# BBUNO.net
KiCad netlist of a schematic drawn in EAGLE
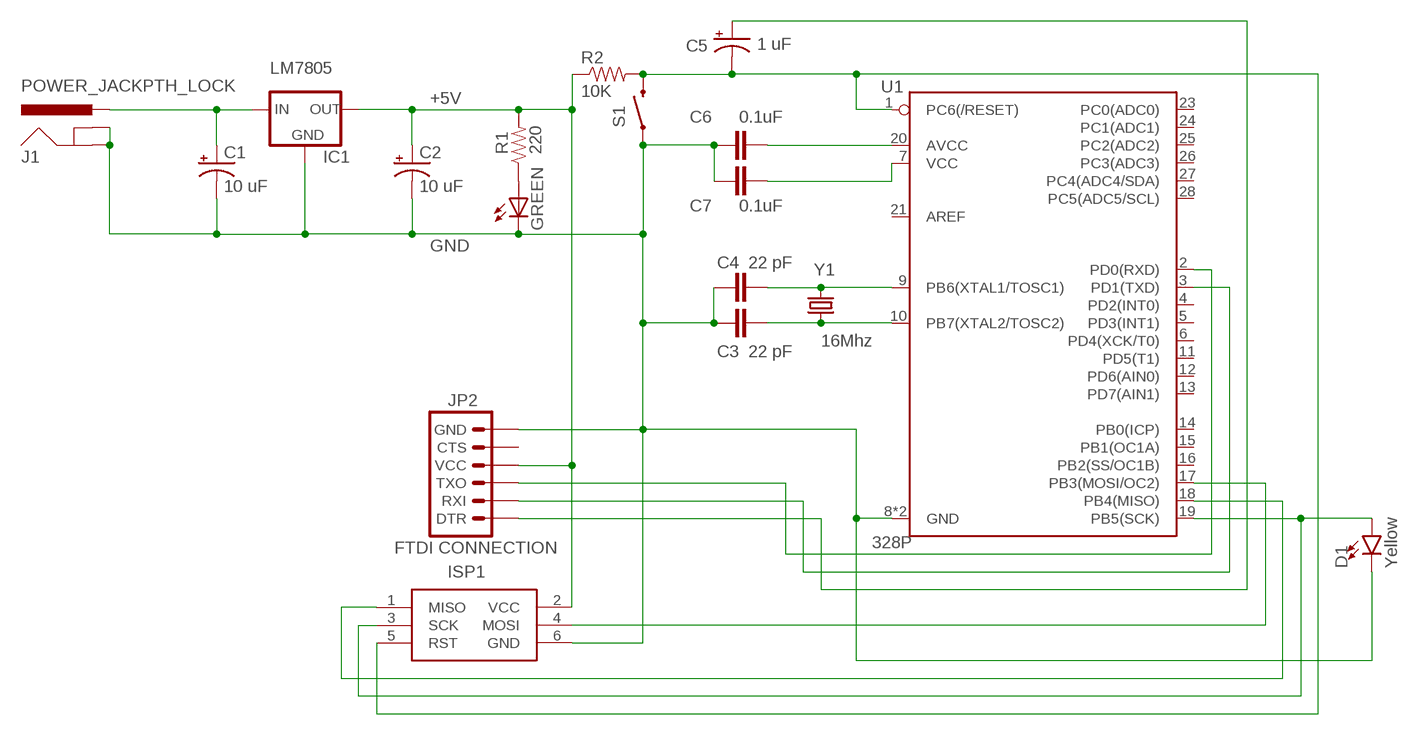
[diagram p0: schematic, sheet 1]

(export (version "E")
  (design (tool "Eeschema 10.0.6"))
  (components
    (comp (ref "C1")
      (value "10 uF")
      (footprint "eagle-import:VISHAY_C")
      (libsource (lib "eagle-import") (part "CAP_POLSMD"))
    )
    (comp (ref "C2")
      (value "10 uF")
      (footprint "eagle-import:VISHAY_C")
      (libsource (lib "eagle-import") (part "CAP_POLSMD"))
    )
    (comp (ref "C3")
      (value "22 pF")
      (footprint "eagle-import:CAP-PTH-5MM")
      (libsource (lib "eagle-import") (part "CAPPTH1"))
    )
    (comp (ref "C4")
      (value "22 pF")
      (footprint "eagle-import:CAP-PTH-5MM")
      (libsource (lib "eagle-import") (part "CAPPTH1"))
    )
    (comp (ref "C5")
      (value "1 uF")
      (footprint "eagle-import:CPOL-RADIAL-100UF-25V")
      (libsource (lib "eagle-import") (part "CAP_POLPTH1"))
    )
    (comp (ref "C6")
      (value "0.1uF")
      (footprint "eagle-import:0603")
      (libsource (lib "eagle-import") (part "0.1UF-0603-50V-10%-X7R-WE"))
    )
    (comp (ref "C7")
      (value "0.1uF")
      (footprint "eagle-import:0603")
      (libsource (lib "eagle-import") (part "0.1UF-0603-50V-10%-X7R-WE"))
    )
    (comp (ref "D1")
      (value "Yellow")
      (footprint "eagle-import:LED-0603")
      (libsource (lib "eagle-import") (part "LED-YELLOW0603"))
    )
    (comp (ref "GREEN")
      (value "LED3MM")
      (footprint "eagle-import:LED3MM")
      (libsource (lib "eagle-import") (part "LED3MM"))
    )
    (comp (ref "IC1")
      (value "LM7805")
      (footprint "eagle-import:TO-220-ALT")
      (libsource (lib "eagle-import") (part "V_REG_78XX-TO-220"))
    )
    (comp (ref "ISP1")
      (value "ADAFRUIT_AVRISP-BOX")
      (footprint "eagle-import:ADAFRUIT_AVRISP-BOX")
      (libsource (lib "eagle-import") (part "ADAFRUIT_AVRISP-BOX"))
    )
    (comp (ref "J1")
      (value "POWER_JACKPTH_LOCK")
      (footprint "eagle-import:POWER_JACK_PTH_LOCK")
      (libsource (lib "eagle-import") (part "POWER_JACKPTH_LOCK"))
    )
    (comp (ref "JP2")
      (value "FTDI CONNECTION")
      (footprint "eagle-import:1X06")
      (libsource (lib "eagle-import") (part "ARDUINO_SERIAL_PROGRAMPTH"))
    )
    (comp (ref "R1")
      (value "220")
      (footprint "eagle-import:AXIAL-0.4")
      (libsource (lib "eagle-import") (part "RESISTORPTH-1/4W"))
    )
    (comp (ref "R2")
      (value "10K")
      (footprint "eagle-import:AXIAL-0.4")
      (libsource (lib "eagle-import") (part "RESISTORPTH-1/4W"))
    )
    (comp (ref "S1")
      (value "SWITCH-MOMENTARY-2PTH")
      (footprint "eagle-import:TACTILE-PTH")
      (libsource (lib "eagle-import") (part "SWITCH-MOMENTARY-2PTH"))
    )
    (comp (ref "U1")
      (value "328P")
      (footprint "eagle-import:DIP28")
      (libsource (lib "eagle-import") (part "ATMEGA328P_PDIP"))
    )
    (comp (ref "Y1")
      (value "16Mhz")
      (footprint "eagle-import:HC49US")
      (libsource (lib "eagle-import") (part "CRYSTALHC49US"))
    )
  )
  (nets
    (net (code "1") (name "/+5V") (class "Default")
      (node (ref "C2") (pin "+") (pinfunction "+_+") (pintype "passive"))
      (node (ref "IC1") (pin "OUT") (pinfunction "OUT_OUT") (pintype "output"))
      (node (ref "ISP1") (pin "2") (pinfunction "VCC_2") (pintype "power_in"))
      (node (ref "JP2") (pin "4") (pinfunction "VCC_4") (pintype "passive"))
      (node (ref "R1") (pin "P$2") (pinfunction "2_P$2") (pintype "passive"))
      (node (ref "R2") (pin "P$1") (pinfunction "1_P$1") (pintype "passive"))
    )
    (net (code "2") (name "/GND") (class "Default")
      (node (ref "C1") (pin "-") (pinfunction "-_-") (pintype "passive"))
      (node (ref "C2") (pin "-") (pinfunction "-_-") (pintype "passive"))
      (node (ref "C3") (pin "2") (pinfunction "2_2") (pintype "passive"))
      (node (ref "C4") (pin "2") (pinfunction "2_2") (pintype "passive"))
      (node (ref "C6") (pin "1") (pinfunction "1_1") (pintype "passive"))
      (node (ref "C7") (pin "1") (pinfunction "1_1") (pintype "passive"))
      (node (ref "D1") (pin "C") (pinfunction "C_C") (pintype "passive"))
      (node (ref "GREEN") (pin "K") (pinfunction "C_K") (pintype "passive"))
      (node (ref "IC1") (pin "GND") (pinfunction "GND_GND") (pintype "input"))
      (node (ref "ISP1") (pin "6") (pinfunction "GND_6") (pintype "power_in"))
      (node (ref "J1") (pin "GND") (pinfunction "GND_GND") (pintype "bidirectional"))
      (node (ref "J1") (pin "GNDBREAK") (pinfunction "GNDBREAK_GNDBREAK") (pintype "bidirectional"))
      (node (ref "JP2") (pin "6") (pinfunction "GND_6") (pintype "passive"))
      (node (ref "S1") (pin "1") (pinfunction "1_1") (pintype "passive"))
      (node (ref "U1") (pin "22") (pinfunction "GND_22") (pintype "bidirectional"))
      (node (ref "U1") (pin "8") (pinfunction "GND_8") (pintype "bidirectional"))
    )
    (net (code "3") (name "Net-(C1-Pad+)") (class "Default")
      (node (ref "C1") (pin "+") (pinfunction "+_+") (pintype "passive"))
      (node (ref "IC1") (pin "IN") (pinfunction "IN_IN") (pintype "input"))
      (node (ref "J1") (pin "PWR") (pinfunction "PWR_PWR") (pintype "bidirectional"))
    )
    (net (code "4") (name "Net-(C5-+)") (class "Default")
      (node (ref "C5") (pin "1") (pinfunction "+_1") (pintype "passive"))
      (node (ref "JP2") (pin "1") (pinfunction "DTR_1") (pintype "passive"))
    )
    (net (code "5") (name "Net-(C5--)") (class "Default")
      (node (ref "C5") (pin "2") (pinfunction "-_2") (pintype "passive"))
      (node (ref "ISP1") (pin "5") (pinfunction "RST_5") (pintype "output"))
      (node (ref "R2") (pin "P$2") (pinfunction "2_P$2") (pintype "passive"))
      (node (ref "S1") (pin "3") (pinfunction "2_3") (pintype "passive"))
      (node (ref "U1") (pin "1") (pinfunction "PC6(/RESET)_1") (pintype "bidirectional"))
    )
    (net (code "6") (name "Net-(ISP1-MISO)") (class "Default")
      (node (ref "ISP1") (pin "1") (pinfunction "MISO_1") (pintype "input"))
      (node (ref "U1") (pin "18") (pinfunction "PB4(MISO)_18") (pintype "bidirectional"))
    )
    (net (code "7") (name "Net-(ISP1-MOSI)") (class "Default")
      (node (ref "ISP1") (pin "4") (pinfunction "MOSI_4") (pintype "output"))
      (node (ref "U1") (pin "17") (pinfunction "PB3(MOSI/OC2)_17") (pintype "bidirectional"))
    )
    (net (code "8") (name "Net-(ISP1-SCK)") (class "Default")
      (node (ref "D1") (pin "A") (pinfunction "A_A") (pintype "passive"))
      (node (ref "ISP1") (pin "3") (pinfunction "SCK_3") (pintype "output"))
      (node (ref "U1") (pin "19") (pinfunction "PB5(SCK)_19") (pintype "bidirectional"))
    )
    (net (code "9") (name "Net-(JP2-RXI)") (class "Default")
      (node (ref "JP2") (pin "2") (pinfunction "RXI_2") (pintype "passive"))
      (node (ref "U1") (pin "3") (pinfunction "PD1(TXD)_3") (pintype "bidirectional"))
    )
    (net (code "10") (name "Net-(JP2-TXO)") (class "Default")
      (node (ref "JP2") (pin "3") (pinfunction "TXO_3") (pintype "passive"))
      (node (ref "U1") (pin "2") (pinfunction "PD0(RXD)_2") (pintype "bidirectional"))
    )
    (net (code "11") (name "Net-(R1-1)") (class "Default")
      (node (ref "GREEN") (pin "A") (pinfunction "A_A") (pintype "passive"))
      (node (ref "R1") (pin "P$1") (pinfunction "1_P$1") (pintype "passive"))
    )
    (net (code "12") (name "Net-(U1-AVCC)") (class "Default")
      (node (ref "C6") (pin "2") (pinfunction "2_2") (pintype "passive"))
      (node (ref "U1") (pin "20") (pinfunction "AVCC_20") (pintype "bidirectional"))
    )
    (net (code "13") (name "Net-(U1-PB6(XTAL1{slash}TOSC1))") (class "Default")
      (node (ref "C4") (pin "1") (pinfunction "1_1") (pintype "passive"))
      (node (ref "U1") (pin "9") (pinfunction "PB6(XTAL1/TOSC1)_9") (pintype "bidirectional"))
      (node (ref "Y1") (pin "2") (pinfunction "2_2") (pintype "passive"))
    )
    (net (code "14") (name "Net-(U1-PB7(XTAL2{slash}TOSC2))") (class "Default")
      (node (ref "C3") (pin "1") (pinfunction "1_1") (pintype "passive"))
      (node (ref "U1") (pin "10") (pinfunction "PB7(XTAL2/TOSC2)_10") (pintype "bidirectional"))
      (node (ref "Y1") (pin "1") (pinfunction "1_1") (pintype "passive"))
    )
    (net (code "15") (name "Net-(U1-VCC)") (class "Default")
      (node (ref "C7") (pin "2") (pinfunction "2_2") (pintype "passive"))
      (node (ref "U1") (pin "7") (pinfunction "VCC_7") (pintype "bidirectional"))
    )
    (net (code "16") (name "unconnected-(JP2-CTS-Pad5)") (class "Default")
      (node (ref "JP2") (pin "5") (pinfunction "CTS_5") (pintype "passive"))
    )
    (net (code "17") (name "unconnected-(U1-AREF-Pad21)") (class "Default")
      (node (ref "U1") (pin "21") (pinfunction "AREF_21") (pintype "bidirectional"))
    )
    (net (code "18") (name "unconnected-(U1-PB0(ICP)-Pad14)") (class "Default")
      (node (ref "U1") (pin "14") (pinfunction "PB0(ICP)_14") (pintype "bidirectional"))
    )
    (net (code "19") (name "unconnected-(U1-PB1(OC1A)-Pad15)") (class "Default")
      (node (ref "U1") (pin "15") (pinfunction "PB1(OC1A)_15") (pintype "bidirectional"))
    )
    (net (code "20") (name "unconnected-(U1-PB2(SS{slash}OC1B)-Pad16)") (class "Default")
      (node (ref "U1") (pin "16") (pinfunction "PB2(SS/OC1B)_16") (pintype "bidirectional"))
    )
    (net (code "21") (name "unconnected-(U1-PC0(ADC0)-Pad23)") (class "Default")
      (node (ref "U1") (pin "23") (pinfunction "PC0(ADC0)_23") (pintype "bidirectional"))
    )
    (net (code "22") (name "unconnected-(U1-PC1(ADC1)-Pad24)") (class "Default")
      (node (ref "U1") (pin "24") (pinfunction "PC1(ADC1)_24") (pintype "bidirectional"))
    )
    (net (code "23") (name "unconnected-(U1-PC2(ADC2)-Pad25)") (class "Default")
      (node (ref "U1") (pin "25") (pinfunction "PC2(ADC2)_25") (pintype "bidirectional"))
    )
    (net (code "24") (name "unconnected-(U1-PC3(ADC3)-Pad26)") (class "Default")
      (node (ref "U1") (pin "26") (pinfunction "PC3(ADC3)_26") (pintype "bidirectional"))
    )
    (net (code "25") (name "unconnected-(U1-PC4(ADC4{slash}SDA)-Pad27)") (class "Default")
      (node (ref "U1") (pin "27") (pinfunction "PC4(ADC4/SDA)_27") (pintype "bidirectional"))
    )
    (net (code "26") (name "unconnected-(U1-PC5(ADC5{slash}SCL)-Pad28)") (class "Default")
      (node (ref "U1") (pin "28") (pinfunction "PC5(ADC5/SCL)_28") (pintype "bidirectional"))
    )
    (net (code "27") (name "unconnected-(U1-PD2(INT0)-Pad4)") (class "Default")
      (node (ref "U1") (pin "4") (pinfunction "PD2(INT0)_4") (pintype "bidirectional"))
    )
    (net (code "28") (name "unconnected-(U1-PD3(INT1)-Pad5)") (class "Default")
      (node (ref "U1") (pin "5") (pinfunction "PD3(INT1)_5") (pintype "bidirectional"))
    )
    (net (code "29") (name "unconnected-(U1-PD4(XCK{slash}T0)-Pad6)") (class "Default")
      (node (ref "U1") (pin "6") (pinfunction "PD4(XCK/T0)_6") (pintype "bidirectional"))
    )
    (net (code "30") (name "unconnected-(U1-PD5(T1)-Pad11)") (class "Default")
      (node (ref "U1") (pin "11") (pinfunction "PD5(T1)_11") (pintype "bidirectional"))
    )
    (net (code "31") (name "unconnected-(U1-PD6(AIN0)-Pad12)") (class "Default")
      (node (ref "U1") (pin "12") (pinfunction "PD6(AIN0)_12") (pintype "bidirectional"))
    )
    (net (code "32") (name "unconnected-(U1-PD7(AIN1)-Pad13)") (class "Default")
      (node (ref "U1") (pin "13") (pinfunction "PD7(AIN1)_13") (pintype "bidirectional"))
    )
  )
)
